# Power.net
KiCad netlist of a schematic drawn in Altium Designer
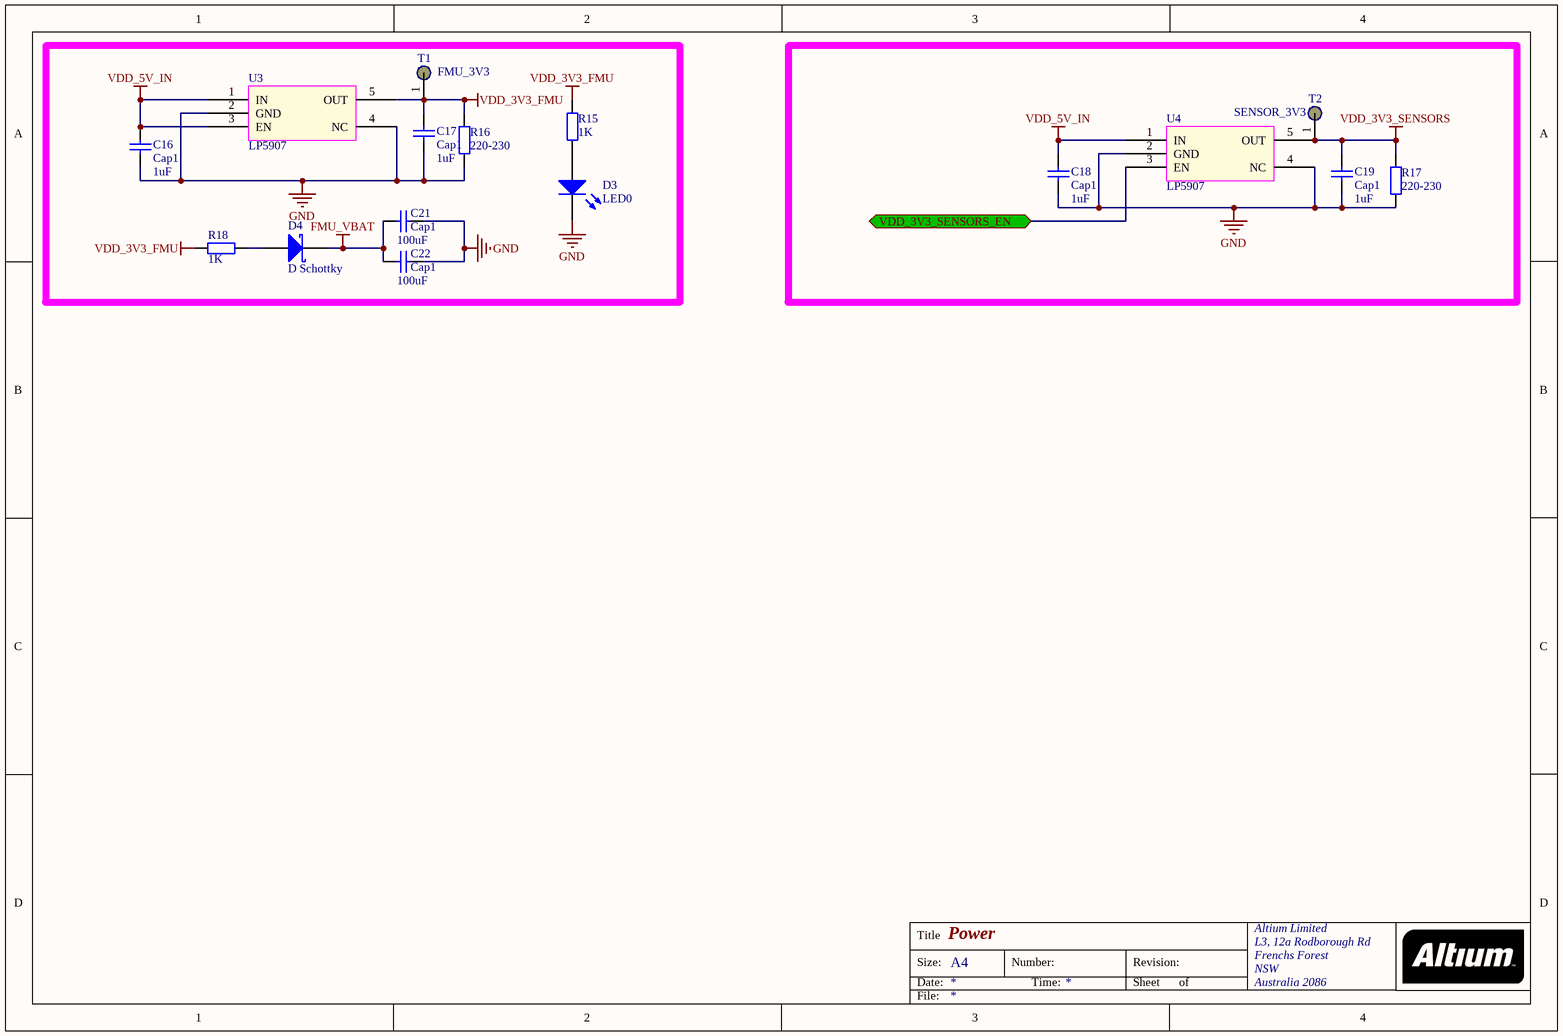
[diagram p0: Power.SchDoc]

(export (version "E")
  (design (tool "Eeschema 10.0.6"))
  (components
    (comp (ref "C16")
      (value "Cap1")
      (footprint "0603AC")
      (description "Capacitor")
      (fields (field (name "ALTIUM_VALUE") "1uF") (field (name "PUBLISHER") "Altium Limited"))
      (libsource (lib "Component") (part "Cap1"))
    )
    (comp (ref "C17")
      (value "Cap1")
      (footprint "0603AC")
      (description "Capacitor")
      (fields (field (name "ALTIUM_VALUE") "1uF") (field (name "PUBLISHER") "Altium Limited"))
      (libsource (lib "Component") (part "Cap1"))
    )
    (comp (ref "C18")
      (value "Cap1")
      (footprint "0603AC")
      (description "Capacitor")
      (fields (field (name "ALTIUM_VALUE") "1uF") (field (name "PUBLISHER") "Altium Limited"))
      (libsource (lib "Component") (part "Cap1"))
    )
    (comp (ref "C19")
      (value "Cap1")
      (footprint "0603AC")
      (description "Capacitor")
      (fields (field (name "ALTIUM_VALUE") "1uF") (field (name "PUBLISHER") "Altium Limited"))
      (libsource (lib "Component") (part "Cap1"))
    )
    (comp (ref "C21")
      (value "Cap1")
      (footprint "0805C")
      (description "Capacitor")
      (fields (field (name "ALTIUM_VALUE") "100uF") (field (name "PUBLISHER") "Altium Limited"))
      (libsource (lib "Component") (part "Cap1"))
    )
    (comp (ref "C22")
      (value "Cap1")
      (footprint "0805C")
      (description "Capacitor")
      (fields (field (name "ALTIUM_VALUE") "100uF") (field (name "PUBLISHER") "Altium Limited"))
      (libsource (lib "Component") (part "Cap1"))
    )
    (comp (ref "D3")
      (value "LED0")
      (footprint "LED_R")
      (description "Typical INFRARED GaAs LED")
      (fields (field (name "PUBLISHER") "Altium Limited"))
      (libsource (lib "Component") (part "LED0"))
    )
    (comp (ref "D4")
      (value "D Schottky")
      (footprint "DO-214")
      (description "Schottky Diode")
      (fields (field (name "PUBLISHER") "Altium Limited"))
      (libsource (lib "Component") (part "D Schottky"))
    )
    (comp (ref "R15")
      (value "1K")
      (footprint "0603AR")
      (fields (field (name "Comment") "Resist"))
      (libsource (lib "Component") (part "Res"))
    )
    (comp (ref "R16")
      (value "220-230")
      (footprint "0603AR")
      (fields (field (name "Comment") "Resist"))
      (libsource (lib "Component") (part "Res"))
    )
    (comp (ref "R17")
      (value "220-230")
      (footprint "0603AR")
      (fields (field (name "Comment") "Resist"))
      (libsource (lib "Component") (part "Res"))
    )
    (comp (ref "R18")
      (value "1K")
      (footprint "0603AR")
      (fields (field (name "Comment") "Resist"))
      (libsource (lib "") (part "Res_1"))
    )
    (comp (ref "T1") (value "FMU_3V3") (footprint "TAB") (libsource (lib "Component") (part "Tap")))
    (comp (ref "T2") (value "SENSOR_3V3") (footprint "TAB") (libsource (lib "Component") (part "Tap")))
    (comp (ref "U3") (value "LP5907") (libsource (lib "Power") (part "LP5907")))
    (comp (ref "U4") (value "LP5907") (libsource (lib "Power") (part "LP5907")))
  )
  (nets
    (net (code "1") (name "/VDD_3V3_SENSORS_EN") (class "Default")
      (node (ref "U4") (pin "3") (pinfunction "EN_3") (pintype "passive"))
    )
    (net (code "2") (name "FMU_VBAT") (class "Default")
      (node (ref "C21") (pin "2") (pinfunction "2_2") (pintype "passive"))
      (node (ref "C22") (pin "2") (pinfunction "2_2") (pintype "passive"))
      (node (ref "D4") (pin "2") (pinfunction "K_2") (pintype "passive"))
    )
    (net (code "3") (name "GND") (class "Default")
      (node (ref "C16") (pin "1") (pinfunction "1_1") (pintype "passive"))
      (node (ref "C17") (pin "1") (pinfunction "1_1") (pintype "passive"))
      (node (ref "C18") (pin "1") (pinfunction "1_1") (pintype "passive"))
      (node (ref "C19") (pin "1") (pinfunction "1_1") (pintype "passive"))
      (node (ref "C21") (pin "1") (pinfunction "1_1") (pintype "passive"))
      (node (ref "C22") (pin "1") (pinfunction "1_1") (pintype "passive"))
      (node (ref "D3") (pin "2") (pinfunction "K_2") (pintype "passive"))
      (node (ref "R16") (pin "1") (pinfunction "1_1") (pintype "passive"))
      (node (ref "R17") (pin "1") (pinfunction "1_1") (pintype "passive"))
      (node (ref "U3") (pin "2") (pinfunction "GND_2") (pintype "passive"))
      (node (ref "U3") (pin "4") (pinfunction "NC_4") (pintype "passive"))
      (node (ref "U4") (pin "2") (pinfunction "GND_2") (pintype "passive"))
      (node (ref "U4") (pin "4") (pinfunction "NC_4") (pintype "passive"))
    )
    (net (code "4") (name "Net-(D3-A)") (class "Default")
      (node (ref "D3") (pin "1") (pinfunction "A_1") (pintype "passive"))
      (node (ref "R15") (pin "1") (pinfunction "1_1") (pintype "passive"))
    )
    (net (code "5") (name "Net-(D4-A)") (class "Default")
      (node (ref "D4") (pin "1") (pinfunction "A_1") (pintype "passive"))
      (node (ref "R18") (pin "1") (pinfunction "1_1") (pintype "passive"))
    )
    (net (code "6") (name "VDD_3V3_FMU") (class "Default")
      (node (ref "C17") (pin "2") (pinfunction "2_2") (pintype "passive"))
      (node (ref "R15") (pin "2") (pinfunction "2_2") (pintype "passive"))
      (node (ref "R16") (pin "2") (pinfunction "2_2") (pintype "passive"))
      (node (ref "R18") (pin "2") (pinfunction "2_2") (pintype "passive"))
      (node (ref "T1") (pin "1") (pinfunction "1_1") (pintype "passive"))
      (node (ref "U3") (pin "5") (pinfunction "OUT_5") (pintype "passive"))
    )
    (net (code "7") (name "VDD_3V3_SENSORS") (class "Default")
      (node (ref "C19") (pin "2") (pinfunction "2_2") (pintype "passive"))
      (node (ref "R17") (pin "2") (pinfunction "2_2") (pintype "passive"))
      (node (ref "T2") (pin "1") (pinfunction "1_1") (pintype "passive"))
      (node (ref "U4") (pin "5") (pinfunction "OUT_5") (pintype "passive"))
    )
    (net (code "8") (name "VDD_5V_IN") (class "Default")
      (node (ref "C16") (pin "2") (pinfunction "2_2") (pintype "passive"))
      (node (ref "C18") (pin "2") (pinfunction "2_2") (pintype "passive"))
      (node (ref "U3") (pin "1") (pinfunction "IN_1") (pintype "passive"))
      (node (ref "U3") (pin "3") (pinfunction "EN_3") (pintype "passive"))
      (node (ref "U4") (pin "1") (pinfunction "IN_1") (pintype "passive"))
    )
  )
)
